# r00tz_v1.net
KiCad netlist of a schematic drawn in EAGLE
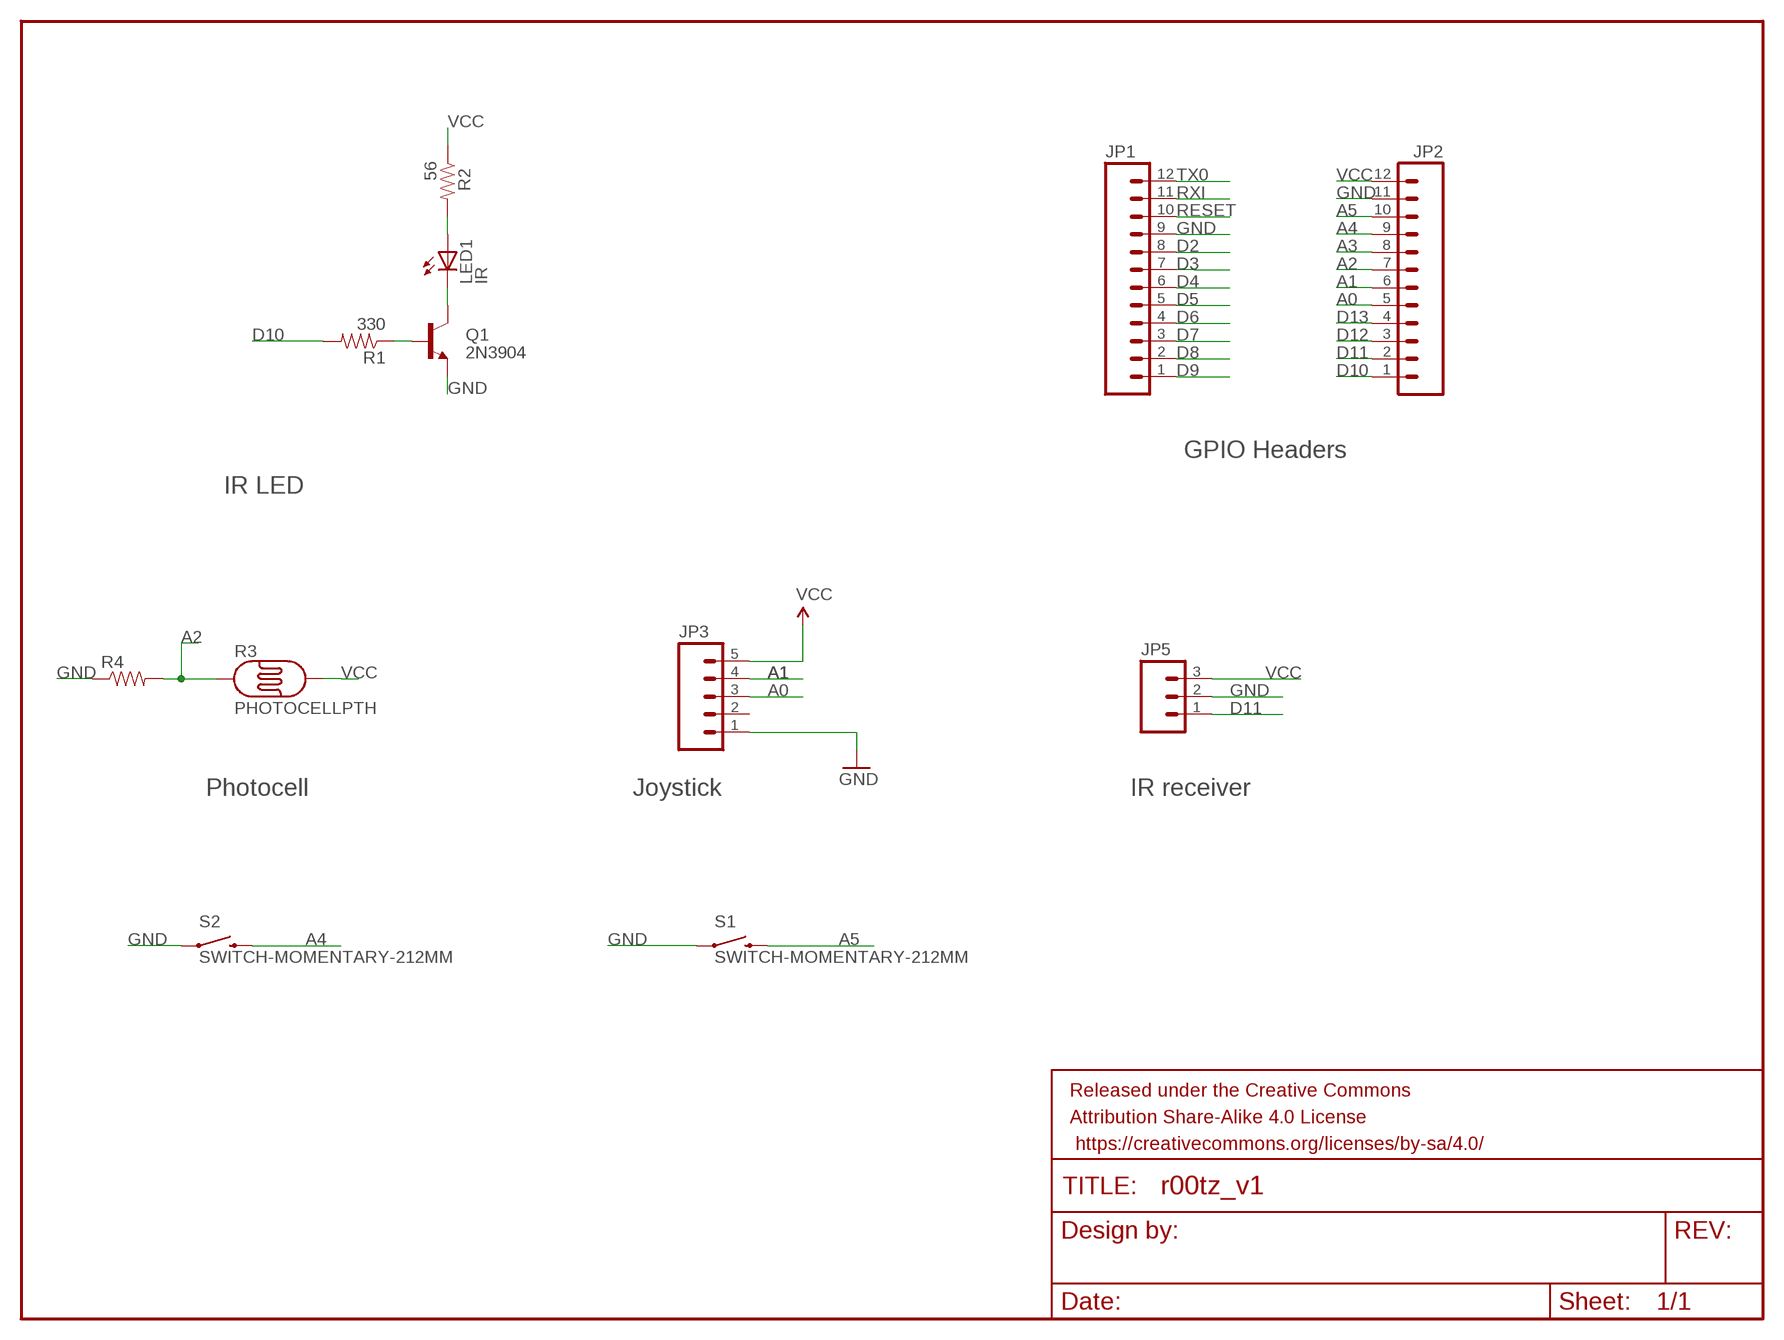
[diagram p0: schematic, sheet 1]

(export (version "E")
  (design (tool "Eeschema 10.0.6"))
  (components
    (comp (ref "FRAME1")
      (value "FRAME-LETTER")
      (footprint "eagle-import:CREATIVE_COMMONS")
      (fields (field (name "DESIGNER") "NAME"))
      (libsource (lib "eagle-import") (part "FRAME-LETTER"))
    )
    (comp (ref "JP1")
      (value "M12PTH")
      (footprint "eagle-import:1X12")
      (libsource (lib "eagle-import") (part "M12PTH"))
    )
    (comp (ref "JP2")
      (value "M12PTH")
      (footprint "eagle-import:1X12")
      (libsource (lib "eagle-import") (part "M12PTH"))
    )
    (comp (ref "JP3")
      (value "M05PTH")
      (footprint "eagle-import:1X05")
      (libsource (lib "eagle-import") (part "M05PTH"))
    )
    (comp (ref "JP5")
      (value "M03PTH")
      (footprint "eagle-import:1X03")
      (libsource (lib "eagle-import") (part "M03PTH"))
    )
    (comp (ref "LED1")
      (value "IR")
      (footprint "eagle-import:LED5MM")
      (libsource (lib "eagle-import") (part "LED5MM"))
    )
    (comp (ref "Q1")
      (value "2N3904")
      (footprint "eagle-import:TO-92")
      (libsource (lib "eagle-import") (part "TRANSISTOR_NPNTO92"))
    )
    (comp (ref "R1")
      (value "330")
      (footprint "eagle-import:AXIAL-0.3")
      (libsource (lib "eagle-import") (part "RESISTORAXIAL-0.3"))
    )
    (comp (ref "R2")
      (value "56")
      (footprint "eagle-import:AXIAL-0.3")
      (libsource (lib "eagle-import") (part "RESISTORAXIAL-0.3"))
    )
    (comp (ref "R3")
      (value "PHOTOCELLPTH")
      (footprint "eagle-import:PHOTOCELL")
      (libsource (lib "eagle-import") (part "PHOTOCELLPTH"))
    )
    (comp (ref "R4")
      (value "10KOHM-1/6W-5%(PTH)KIT")
      (footprint "eagle-import:AXIAL-0.3-KIT")
      (libsource (lib "eagle-import") (part "10KOHM-1/6W-5%(PTH)KIT"))
    )
    (comp (ref "S1")
      (value "SWITCH-MOMENTARY-212MM")
      (footprint "eagle-import:TACTILE-PTH-12MM")
      (libsource (lib "eagle-import") (part "SWITCH-MOMENTARY-212MM"))
    )
    (comp (ref "S2")
      (value "SWITCH-MOMENTARY-212MM")
      (footprint "eagle-import:TACTILE-PTH-12MM")
      (libsource (lib "eagle-import") (part "SWITCH-MOMENTARY-212MM"))
    )
  )
  (nets
    (net (code "1") (name "/A0") (class "Default")
      (node (ref "JP2") (pin "5") (pinfunction "5_5") (pintype "passive"))
      (node (ref "JP3") (pin "3") (pinfunction "3_3") (pintype "passive"))
    )
    (net (code "2") (name "/A1") (class "Default")
      (node (ref "JP2") (pin "6") (pinfunction "6_6") (pintype "passive"))
      (node (ref "JP3") (pin "4") (pinfunction "4_4") (pintype "passive"))
    )
    (net (code "3") (name "/A2") (class "Default")
      (node (ref "JP2") (pin "7") (pinfunction "7_7") (pintype "passive"))
      (node (ref "R3") (pin "1") (pinfunction "P$1_1") (pintype "bidirectional"))
      (node (ref "R4") (pin "P$2") (pinfunction "2_P$2") (pintype "passive"))
    )
    (net (code "4") (name "/A3") (class "Default")
      (node (ref "JP2") (pin "8") (pinfunction "8_8") (pintype "passive"))
    )
    (net (code "5") (name "/A4") (class "Default")
      (node (ref "JP2") (pin "9") (pinfunction "9_9") (pintype "passive"))
      (node (ref "S2") (pin "3") (pinfunction "2_3") (pintype "passive"))
    )
    (net (code "6") (name "/A5") (class "Default")
      (node (ref "JP2") (pin "10") (pinfunction "10_10") (pintype "passive"))
      (node (ref "S1") (pin "3") (pinfunction "2_3") (pintype "passive"))
    )
    (net (code "7") (name "/D2") (class "Default")
      (node (ref "JP1") (pin "8") (pinfunction "8_8") (pintype "passive"))
    )
    (net (code "8") (name "/D3") (class "Default")
      (node (ref "JP1") (pin "7") (pinfunction "7_7") (pintype "passive"))
    )
    (net (code "9") (name "/D4") (class "Default")
      (node (ref "JP1") (pin "6") (pinfunction "6_6") (pintype "passive"))
    )
    (net (code "10") (name "/D5") (class "Default")
      (node (ref "JP1") (pin "5") (pinfunction "5_5") (pintype "passive"))
    )
    (net (code "11") (name "/D6") (class "Default")
      (node (ref "JP1") (pin "4") (pinfunction "4_4") (pintype "passive"))
    )
    (net (code "12") (name "/D7") (class "Default")
      (node (ref "JP1") (pin "3") (pinfunction "3_3") (pintype "passive"))
    )
    (net (code "13") (name "/D8") (class "Default")
      (node (ref "JP1") (pin "2") (pinfunction "2_2") (pintype "passive"))
    )
    (net (code "14") (name "/D9") (class "Default")
      (node (ref "JP1") (pin "1") (pinfunction "1_1") (pintype "passive"))
    )
    (net (code "15") (name "/D10") (class "Default")
      (node (ref "JP2") (pin "1") (pinfunction "1_1") (pintype "passive"))
      (node (ref "R1") (pin "P$2") (pinfunction "2_P$2") (pintype "passive"))
    )
    (net (code "16") (name "/D11") (class "Default")
      (node (ref "JP2") (pin "2") (pinfunction "2_2") (pintype "passive"))
      (node (ref "JP5") (pin "1") (pinfunction "1_1") (pintype "passive"))
    )
    (net (code "17") (name "/D12") (class "Default")
      (node (ref "JP2") (pin "3") (pinfunction "3_3") (pintype "passive"))
    )
    (net (code "18") (name "/D13") (class "Default")
      (node (ref "JP2") (pin "4") (pinfunction "4_4") (pintype "passive"))
    )
    (net (code "19") (name "/RESET") (class "Default")
      (node (ref "JP1") (pin "10") (pinfunction "10_10") (pintype "passive"))
    )
    (net (code "20") (name "/RXI") (class "Default")
      (node (ref "JP1") (pin "11") (pinfunction "11_11") (pintype "passive"))
    )
    (net (code "21") (name "/TX0") (class "Default")
      (node (ref "JP1") (pin "12") (pinfunction "12_12") (pintype "passive"))
    )
    (net (code "22") (name "GND") (class "Default")
      (node (ref "JP1") (pin "9") (pinfunction "9_9") (pintype "passive"))
      (node (ref "JP2") (pin "11") (pinfunction "11_11") (pintype "passive"))
      (node (ref "JP3") (pin "1") (pinfunction "1_1") (pintype "passive"))
      (node (ref "JP5") (pin "2") (pinfunction "2_2") (pintype "passive"))
      (node (ref "Q1") (pin "1") (pinfunction "E_1") (pintype "passive"))
      (node (ref "R4") (pin "P$1") (pinfunction "1_P$1") (pintype "passive"))
      (node (ref "S1") (pin "1") (pinfunction "1_1") (pintype "passive"))
      (node (ref "S2") (pin "1") (pinfunction "1_1") (pintype "passive"))
    )
    (net (code "23") (name "Net-(LED1-C)") (class "Default")
      (node (ref "LED1") (pin "K") (pinfunction "C_K") (pintype "passive"))
      (node (ref "Q1") (pin "3") (pinfunction "C_3") (pintype "passive"))
    )
    (net (code "24") (name "Net-(Q1-B)") (class "Default")
      (node (ref "Q1") (pin "2") (pinfunction "B_2") (pintype "passive"))
      (node (ref "R1") (pin "P$1") (pinfunction "1_P$1") (pintype "passive"))
    )
    (net (code "25") (name "Net-(R2-2)") (class "Default")
      (node (ref "LED1") (pin "A") (pinfunction "A_A") (pintype "passive"))
      (node (ref "R2") (pin "P$2") (pinfunction "2_P$2") (pintype "passive"))
    )
    (net (code "26") (name "VCC") (class "Default")
      (node (ref "JP2") (pin "12") (pinfunction "12_12") (pintype "passive"))
      (node (ref "JP3") (pin "5") (pinfunction "5_5") (pintype "passive"))
      (node (ref "JP5") (pin "3") (pinfunction "3_3") (pintype "passive"))
      (node (ref "R2") (pin "P$1") (pinfunction "1_P$1") (pintype "passive"))
      (node (ref "R3") (pin "2") (pinfunction "P$2_2") (pintype "bidirectional"))
    )
    (net (code "27") (name "unconnected-(JP3-Pad2)") (class "Default")
      (node (ref "JP3") (pin "2") (pinfunction "2_2") (pintype "passive"))
    )
  )
)
